# toy_redesign2.net
KiCad netlist of a schematic drawn in EAGLE
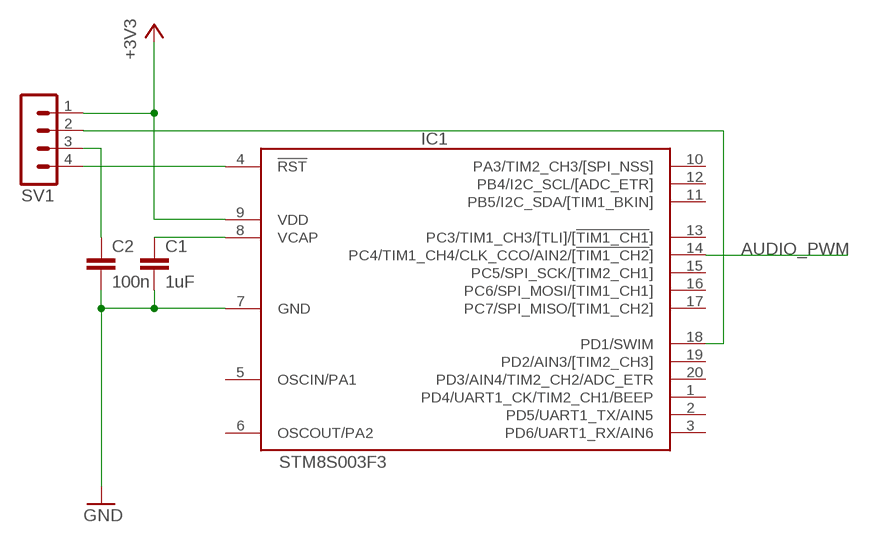
[diagram p0: schematic, sheet 1]

(export (version "E")
  (design (tool "Eeschema 10.0.6"))
  (components
    (comp (ref "C1")
      (value "1uF")
      (footprint "eagle-import:C0805")
      (libsource (lib "eagle-import") (part "C-EUC0805"))
    )
    (comp (ref "C2")
      (value "100n")
      (footprint "eagle-import:C0805")
      (libsource (lib "eagle-import") (part "C-EUC0805"))
    )
    (comp (ref "IC1")
      (value "STM8S003F3")
      (footprint "eagle-import:TSSOP20")
      (libsource (lib "eagle-import") (part "STM8S003F3"))
    )
    (comp (ref "SV1")
      (value "MA04-1")
      (footprint "eagle-import:MA04-1")
      (libsource (lib "eagle-import") (part "MA04-1"))
    )
  )
  (nets
    (net (code "1") (name "+3V3") (class "Default")
      (node (ref "IC1") (pin "9") (pinfunction "VDD_9") (pintype "power_in"))
      (node (ref "SV1") (pin "1") (pinfunction "1_1") (pintype "passive"))
    )
    (net (code "2") (name "/AUDIO_PWM") (class "Default")
      (node (ref "IC1") (pin "14") (pinfunction "PC4/TIM1_CH4/CLK_CCO/AIN2/[~{TIM1_CH2}]_14") (pintype "bidirectional"))
    )
    (net (code "3") (name "GND") (class "Default")
      (node (ref "C1") (pin "2") (pinfunction "2_2") (pintype "passive"))
      (node (ref "C2") (pin "2") (pinfunction "2_2") (pintype "passive"))
      (node (ref "IC1") (pin "7") (pinfunction "GND_7") (pintype "power_in"))
    )
    (net (code "4") (name "Net-(C2-Pad1)") (class "Default")
      (node (ref "C2") (pin "1") (pinfunction "1_1") (pintype "passive"))
      (node (ref "SV1") (pin "3") (pinfunction "3_3") (pintype "passive"))
    )
    (net (code "5") (name "Net-(IC1-PD1{slash}SWIM)") (class "Default")
      (node (ref "IC1") (pin "18") (pinfunction "PD1/SWIM_18") (pintype "bidirectional"))
      (node (ref "SV1") (pin "2") (pinfunction "2_2") (pintype "passive"))
    )
    (net (code "6") (name "Net-(IC1-VCAP)") (class "Default")
      (node (ref "C1") (pin "1") (pinfunction "1_1") (pintype "passive"))
      (node (ref "IC1") (pin "8") (pinfunction "VCAP_8") (pintype "power_in"))
    )
    (net (code "7") (name "Net-(IC1-~{RST})") (class "Default")
      (node (ref "IC1") (pin "4") (pinfunction "~{RST}_4") (pintype "input"))
      (node (ref "SV1") (pin "4") (pinfunction "4_4") (pintype "passive"))
    )
    (net (code "8") (name "unconnected-(IC1-OSCIN{slash}PA1-Pad5)") (class "Default")
      (node (ref "IC1") (pin "5") (pinfunction "OSCIN/PA1_5") (pintype "bidirectional"))
    )
    (net (code "9") (name "unconnected-(IC1-OSCOUT{slash}PA2-Pad6)") (class "Default")
      (node (ref "IC1") (pin "6") (pinfunction "OSCOUT/PA2_6") (pintype "bidirectional"))
    )
    (net (code "10") (name "unconnected-(IC1-PA3{slash}TIM2_CH3{slash}[SPI_NSS]-Pad10)") (class "Default")
      (node (ref "IC1") (pin "10") (pinfunction "PA3/TIM2_CH3/[SPI_NSS]_10") (pintype "bidirectional"))
    )
    (net (code "11") (name "unconnected-(IC1-PB4{slash}I2C_SCL{slash}[ADC_ETR]-Pad12)") (class "Default")
      (node (ref "IC1") (pin "12") (pinfunction "PB4/I2C_SCL/[ADC_ETR]_12") (pintype "bidirectional"))
    )
    (net (code "12") (name "unconnected-(IC1-PB5{slash}I2C_SDA{slash}[TIM1_BKIN]-Pad11)") (class "Default")
      (node (ref "IC1") (pin "11") (pinfunction "PB5/I2C_SDA/[TIM1_BKIN]_11") (pintype "bidirectional"))
    )
    (net (code "13") (name "unconnected-(IC1-PC3{slash}TIM1_CH3{slash}[TLI]{slash}[~{TIM1_CH1}]-Pad13)") (class "Default")
      (node (ref "IC1") (pin "13") (pinfunction "PC3/TIM1_CH3/[TLI]/[~{TIM1_CH1}]_13") (pintype "bidirectional"))
    )
    (net (code "14") (name "unconnected-(IC1-PC5{slash}SPI_SCK{slash}[TIM2_CH1]-Pad15)") (class "Default")
      (node (ref "IC1") (pin "15") (pinfunction "PC5/SPI_SCK/[TIM2_CH1]_15") (pintype "bidirectional"))
    )
    (net (code "15") (name "unconnected-(IC1-PC6{slash}SPI_MOSI{slash}[TIM1_CH1]-Pad16)") (class "Default")
      (node (ref "IC1") (pin "16") (pinfunction "PC6/SPI_MOSI/[TIM1_CH1]_16") (pintype "bidirectional"))
    )
    (net (code "16") (name "unconnected-(IC1-PC7{slash}SPI_MISO{slash}[TIM1_CH2]-Pad17)") (class "Default")
      (node (ref "IC1") (pin "17") (pinfunction "PC7/SPI_MISO/[TIM1_CH2]_17") (pintype "bidirectional"))
    )
    (net (code "17") (name "unconnected-(IC1-PD2{slash}AIN3{slash}[TIM2_CH3]-Pad19)") (class "Default")
      (node (ref "IC1") (pin "19") (pinfunction "PD2/AIN3/[TIM2_CH3]_19") (pintype "bidirectional"))
    )
    (net (code "18") (name "unconnected-(IC1-PD3{slash}AIN4{slash}TIM2_CH2{slash}ADC_ETR-Pad20)") (class "Default")
      (node (ref "IC1") (pin "20") (pinfunction "PD3/AIN4/TIM2_CH2/ADC_ETR_20") (pintype "bidirectional"))
    )
    (net (code "19") (name "unconnected-(IC1-PD4{slash}UART1_CK{slash}TIM2_CH1{slash}BEEP-Pad1)") (class "Default")
      (node (ref "IC1") (pin "1") (pinfunction "PD4/UART1_CK/TIM2_CH1/BEEP_1") (pintype "bidirectional"))
    )
    (net (code "20") (name "unconnected-(IC1-PD5{slash}UART1_TX{slash}AIN5-Pad2)") (class "Default")
      (node (ref "IC1") (pin "2") (pinfunction "PD5/UART1_TX/AIN5_2") (pintype "bidirectional"))
    )
    (net (code "21") (name "unconnected-(IC1-PD6{slash}UART1_RX{slash}AIN6-Pad3)") (class "Default")
      (node (ref "IC1") (pin "3") (pinfunction "PD6/UART1_RX/AIN6_3") (pintype "bidirectional"))
    )
  )
)
